# PCB.net
KiCad netlist of a schematic drawn in Altium Designer
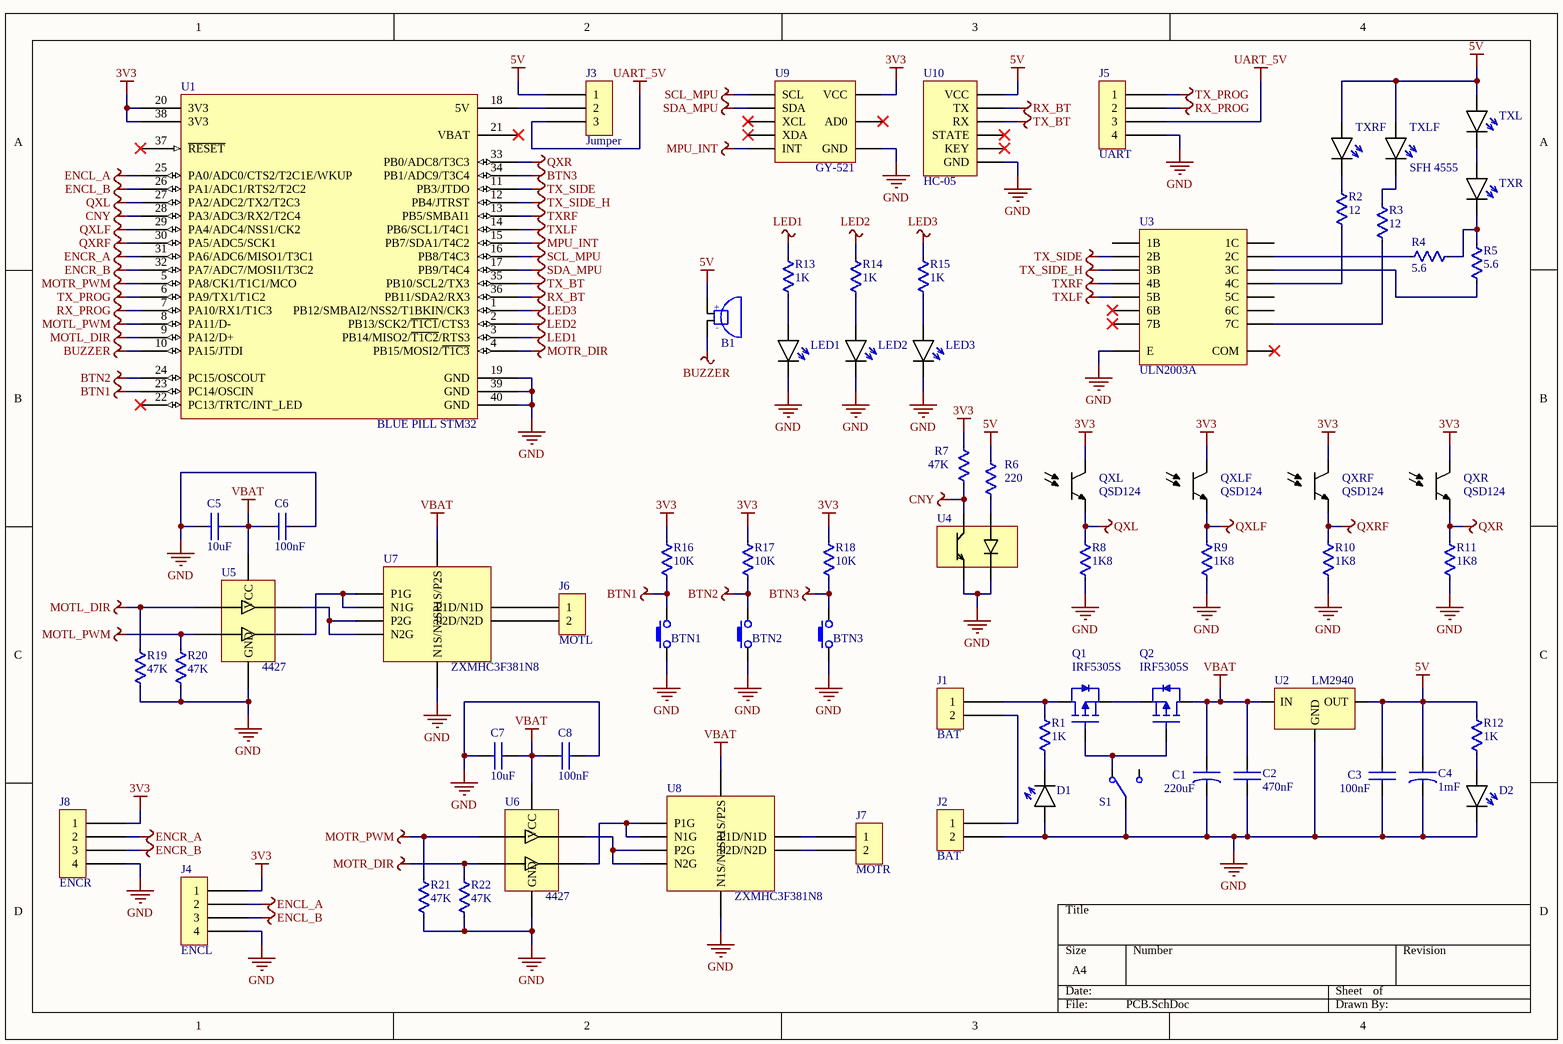
[diagram p0: PCB.SchDoc]

(export (version "E")
  (design (tool "Eeschema 10.0.6"))
  (components
    (comp (ref "B1")
      (value "BUZZER")
      (footprint "BUZZER-12MM")
      (libsource (lib "AltiumLibrary") (part "BUZZER-ACTIVE"))
    )
    (comp (ref "BTN1")
      (value "BUTTON")
      (footprint "TACT_SWITCH-SMALL-4PIN")
      (libsource (lib "AltiumLibrary") (part "BUTTON"))
    )
    (comp (ref "BTN2")
      (value "BUTTON")
      (footprint "TACT_SWITCH-SMALL-4PIN")
      (libsource (lib "AltiumLibrary") (part "BUTTON"))
    )
    (comp (ref "BTN3")
      (value "BUTTON")
      (footprint "TACT_SWITCH-SMALL-4PIN")
      (libsource (lib "AltiumLibrary") (part "BUTTON"))
    )
    (comp (ref "C1")
      (value "220uF")
      (footprint "CAP-ELEC-5x11x2mm")
      (fields (field (name "Comment") "CAP-ELEC"))
      (libsource (lib "AltiumLibrary") (part "CAP-ELEC"))
    )
    (comp (ref "C2")
      (value "470nF")
      (footprint "C1206")
      (fields (field (name "Comment") "CAP-CER"))
      (libsource (lib "AltiumLibrary") (part "CAP-CER"))
    )
    (comp (ref "C3")
      (value "100nF")
      (footprint "C1206")
      (fields (field (name "Comment") "CAP-CER"))
      (libsource (lib "AltiumLibrary") (part "CAP-CER"))
    )
    (comp (ref "C4")
      (value "1mF")
      (footprint "CAP-ELEC-5x11x2mm")
      (fields (field (name "Comment") "CAP-ELEC"))
      (libsource (lib "AltiumLibrary") (part "CAP-ELEC"))
    )
    (comp (ref "C5")
      (value "10uF")
      (footprint "C1206")
      (fields (field (name "Comment") "CAP-CER"))
      (libsource (lib "AltiumLibrary") (part "CAP-CER"))
    )
    (comp (ref "C6")
      (value "100nF")
      (footprint "C1206")
      (fields (field (name "Comment") "CAP-CER"))
      (libsource (lib "AltiumLibrary") (part "CAP-CER"))
    )
    (comp (ref "C7")
      (value "10uF")
      (footprint "C1206")
      (fields (field (name "Comment") "CAP-CER"))
      (libsource (lib "AltiumLibrary") (part "CAP-CER"))
    )
    (comp (ref "C8")
      (value "100nF")
      (footprint "C1206")
      (fields (field (name "Comment") "CAP-CER"))
      (libsource (lib "AltiumLibrary") (part "CAP-CER"))
    )
    (comp (ref "D1") (value "LED") (footprint "LED-3MM-GREEN") (libsource (lib "AltiumLibrary") (part "LED")))
    (comp (ref "D2") (value "LED") (footprint "LED-3MM-GREEN") (libsource (lib "AltiumLibrary") (part "LED")))
    (comp (ref "J1")
      (value "BAT")
      (footprint "HEADER 1x2")
      (libsource (lib "AltiumLibrary") (part "Header 1x2"))
    )
    (comp (ref "J2")
      (value "BAT")
      (footprint "HEADER 1x2")
      (libsource (lib "AltiumLibrary") (part "Header 1x2"))
    )
    (comp (ref "J3")
      (value "Jumper")
      (footprint "Header 1x3")
      (libsource (lib "AltiumLibrary") (part "Header 1x3"))
    )
    (comp (ref "J4")
      (value "ENCL")
      (footprint "Header 1x4")
      (libsource (lib "AltiumLibrary") (part "Header 1x4"))
    )
    (comp (ref "J5")
      (value "UART")
      (footprint "Header 1x4")
      (libsource (lib "AltiumLibrary") (part "Header 1x4"))
    )
    (comp (ref "J6") (value "MOTL") (footprint "HEADER 1x2") (libsource (lib "") (part "Header 1x2_1")))
    (comp (ref "J7") (value "MOTR") (footprint "HEADER 1x2") (libsource (lib "") (part "Header 1x2_1")))
    (comp (ref "J8")
      (value "ENCR")
      (footprint "Header 1x4")
      (libsource (lib "AltiumLibrary") (part "Header 1x4"))
    )
    (comp (ref "LED1")
      (value "LED")
      (footprint "LED-3MM-GREEN")
      (libsource (lib "AltiumLibrary") (part "LED"))
    )
    (comp (ref "LED2")
      (value "LED")
      (footprint "LED-3MM-GREEN")
      (libsource (lib "AltiumLibrary") (part "LED"))
    )
    (comp (ref "LED3")
      (value "LED")
      (footprint "LED-3MM-GREEN")
      (libsource (lib "AltiumLibrary") (part "LED"))
    )
    (comp (ref "Q1")
      (value "IRF5305S")
      (footprint "TO-263")
      (libsource (lib "AltiumLibrary") (part "P-MOSFET"))
    )
    (comp (ref "Q2")
      (value "IRF5305S")
      (footprint "TO-263")
      (libsource (lib "AltiumLibrary") (part "P-MOSFET"))
    )
    (comp (ref "QXL")
      (value "QSD124")
      (footprint "LED-5MM-RED-90-2")
      (libsource (lib "AltiumLibrary") (part "PHOTO NPN"))
    )
    (comp (ref "QXLF")
      (value "QSD124")
      (footprint "LED-5MM-RED-90")
      (libsource (lib "AltiumLibrary") (part "PHOTO NPN"))
    )
    (comp (ref "QXR")
      (value "QSD124")
      (footprint "LED-5MM-RED-90")
      (libsource (lib "AltiumLibrary") (part "PHOTO NPN"))
    )
    (comp (ref "QXRF")
      (value "QSD124")
      (footprint "LED-5MM-RED-90")
      (libsource (lib "AltiumLibrary") (part "PHOTO NPN"))
    )
    (comp (ref "R1")
      (value "1K")
      (footprint "R1206")
      (fields (field (name "Comment") "RES"))
      (libsource (lib "AltiumLibrary") (part "RES"))
    )
    (comp (ref "R2")
      (value "12")
      (footprint "R1206")
      (fields (field (name "Comment") "RES"))
      (libsource (lib "AltiumLibrary") (part "RES"))
    )
    (comp (ref "R3")
      (value "12")
      (footprint "R1206")
      (fields (field (name "Comment") "RES"))
      (libsource (lib "AltiumLibrary") (part "RES"))
    )
    (comp (ref "R4")
      (value "5.6")
      (footprint "R1206")
      (fields (field (name "Comment") "RES"))
      (libsource (lib "") (part "RES_1"))
    )
    (comp (ref "R5")
      (value "5.6")
      (footprint "R1206")
      (fields (field (name "Comment") "RES"))
      (libsource (lib "AltiumLibrary") (part "RES"))
    )
    (comp (ref "R6")
      (value "220")
      (footprint "R1206")
      (fields (field (name "Comment") "RES"))
      (libsource (lib "AltiumLibrary") (part "RES"))
    )
    (comp (ref "R7")
      (value "47K")
      (footprint "R1206")
      (fields (field (name "Comment") "RES"))
      (libsource (lib "AltiumLibrary") (part "RES"))
    )
    (comp (ref "R8")
      (value "1K8")
      (footprint "R1206")
      (fields (field (name "Comment") "RES"))
      (libsource (lib "AltiumLibrary") (part "RES"))
    )
    (comp (ref "R9")
      (value "1K8")
      (footprint "R1206")
      (fields (field (name "Comment") "RES"))
      (libsource (lib "AltiumLibrary") (part "RES"))
    )
    (comp (ref "R10")
      (value "1K8")
      (footprint "R1206")
      (fields (field (name "Comment") "RES"))
      (libsource (lib "AltiumLibrary") (part "RES"))
    )
    (comp (ref "R11")
      (value "1K8")
      (footprint "R1206")
      (fields (field (name "Comment") "RES"))
      (libsource (lib "AltiumLibrary") (part "RES"))
    )
    (comp (ref "R12")
      (value "1K")
      (footprint "R1206")
      (fields (field (name "Comment") "RES"))
      (libsource (lib "AltiumLibrary") (part "RES"))
    )
    (comp (ref "R13")
      (value "1K")
      (footprint "R1206")
      (fields (field (name "Comment") "RES"))
      (libsource (lib "AltiumLibrary") (part "RES"))
    )
    (comp (ref "R14")
      (value "1K")
      (footprint "R1206")
      (fields (field (name "Comment") "RES"))
      (libsource (lib "AltiumLibrary") (part "RES"))
    )
    (comp (ref "R15")
      (value "1K")
      (footprint "R1206")
      (fields (field (name "Comment") "RES"))
      (libsource (lib "AltiumLibrary") (part "RES"))
    )
    (comp (ref "R16")
      (value "10K")
      (footprint "R1206")
      (fields (field (name "Comment") "RES"))
      (libsource (lib "AltiumLibrary") (part "RES"))
    )
    (comp (ref "R17")
      (value "10K")
      (footprint "R1206")
      (fields (field (name "Comment") "RES"))
      (libsource (lib "AltiumLibrary") (part "RES"))
    )
    (comp (ref "R18")
      (value "10K")
      (footprint "R1206")
      (fields (field (name "Comment") "RES"))
      (libsource (lib "AltiumLibrary") (part "RES"))
    )
    (comp (ref "R19")
      (value "47K")
      (footprint "R1206")
      (fields (field (name "Comment") "RES"))
      (libsource (lib "AltiumLibrary") (part "RES"))
    )
    (comp (ref "R20")
      (value "47K")
      (footprint "R1206")
      (fields (field (name "Comment") "RES"))
      (libsource (lib "AltiumLibrary") (part "RES"))
    )
    (comp (ref "R21")
      (value "47K")
      (footprint "R1206")
      (fields (field (name "Comment") "RES"))
      (libsource (lib "AltiumLibrary") (part "RES"))
    )
    (comp (ref "R22")
      (value "47K")
      (footprint "R1206")
      (fields (field (name "Comment") "RES"))
      (libsource (lib "AltiumLibrary") (part "RES"))
    )
    (comp (ref "S1")
      (value "SLIDE-SWITCH")
      (footprint "SWITCH")
      (libsource (lib "AltiumLibrary") (part "SLIDE-SWITCH"))
    )
    (comp (ref "TXL")
      (value "LED")
      (footprint "LED-5MM-RED-90-2")
      (libsource (lib "AltiumLibrary") (part "LED"))
    )
    (comp (ref "TXLF")
      (value "SFH 4555")
      (footprint "LED-5MM-RED-90")
      (libsource (lib "AltiumLibrary") (part "LED"))
    )
    (comp (ref "TXR")
      (value "LED")
      (footprint "LED-5MM-RED-90")
      (libsource (lib "AltiumLibrary") (part "LED"))
    )
    (comp (ref "TXRF")
      (value "LED")
      (footprint "LED-5MM-RED-90")
      (libsource (lib "AltiumLibrary") (part "LED"))
    )
    (comp (ref "U1")
      (value "BLUE PILL STM32")
      (footprint "BLUE_PILL")
      (libsource (lib "AltiumLibrary") (part "BLUE PILL STM32"))
    )
    (comp (ref "U2") (value "LM2940") (footprint "TO-263") (libsource (lib "AltiumLibrary") (part "LM2940")))
    (comp (ref "U3")
      (value "ULN2003A")
      (footprint "SOIC-16-NARROW")
      (libsource (lib "AltiumLibrary") (part "ULN2003A"))
    )
    (comp (ref "U4")
      (value "QRE1113GR")
      (footprint "QRE1113GR")
      (fields (field (name "MF") "ON Semiconductor"))
      (libsource (lib "AltiumLibrary") (part "QRE1113GR"))
    )
    (comp (ref "U5") (value "4427") (footprint "SOIC-8") (libsource (lib "AltiumLibrary") (part "4427")))
    (comp (ref "U6") (value "4427") (footprint "SOIC-8") (libsource (lib "AltiumLibrary") (part "4427")))
    (comp (ref "U7")
      (value "ZXMHC3F381N8")
      (footprint "SOIC-8")
      (libsource (lib "AltiumLibrary") (part "ZXMHC3F381N8"))
    )
    (comp (ref "U8")
      (value "ZXMHC3F381N8")
      (footprint "SOIC-8")
      (libsource (lib "AltiumLibrary") (part "ZXMHC3F381N8"))
    )
    (comp (ref "U9")
      (value "GY-521")
      (footprint "GY-521")
      (libsource (lib "AltiumLibrary") (part "GY-521 (MPU6050)"))
    )
    (comp (ref "U10") (value "HC-05") (footprint "HC-05") (libsource (lib "AltiumLibrary") (part "HC-05")))
  )
  (nets
    (net (code "1") (name "3V3") (class "Default")
      (node (ref "J4") (pin "1") (pinfunction "1_1") (pintype "passive"))
      (node (ref "J8") (pin "1") (pinfunction "1_1") (pintype "passive"))
      (node (ref "QXL") (pin "C") (pinfunction "C_C") (pintype "passive"))
      (node (ref "QXLF") (pin "C") (pinfunction "C_C") (pintype "passive"))
      (node (ref "QXR") (pin "C") (pinfunction "C_C") (pintype "passive"))
      (node (ref "QXRF") (pin "C") (pinfunction "C_C") (pintype "passive"))
      (node (ref "R16") (pin "2") (pintype "passive"))
      (node (ref "R17") (pin "2") (pintype "passive"))
      (node (ref "R18") (pin "2") (pintype "passive"))
      (node (ref "R7") (pin "2") (pintype "passive"))
      (node (ref "U1") (pin "20") (pinfunction "3V3_20") (pintype "power_in"))
      (node (ref "U1") (pin "38") (pinfunction "3V3_38") (pintype "power_in"))
      (node (ref "U9") (pin "1") (pinfunction "VCC_1") (pintype "power_in"))
    )
    (net (code "2") (name "5V") (class "Default")
      (node (ref "B1") (pin "1") (pinfunction "+_1") (pintype "passive"))
      (node (ref "C3") (pin "2") (pintype "passive"))
      (node (ref "C4") (pin "1") (pintype "passive"))
      (node (ref "J3") (pin "1") (pinfunction "1_1") (pintype "passive"))
      (node (ref "R12") (pin "2") (pintype "passive"))
      (node (ref "R6") (pin "2") (pintype "passive"))
      (node (ref "TXL") (pin "A") (pintype "passive"))
      (node (ref "TXLF") (pin "A") (pintype "passive"))
      (node (ref "TXRF") (pin "A") (pintype "passive"))
      (node (ref "U10") (pin "2") (pinfunction "VCC_2") (pintype "power_in"))
      (node (ref "U2") (pin "3") (pinfunction "OUT_3") (pintype "power_in"))
    )
    (net (code "3") (name "BTN1") (class "Default")
      (node (ref "BTN1") (pin "2") (pintype "passive"))
      (node (ref "R16") (pin "1") (pintype "passive"))
      (node (ref "U1") (pin "23") (pinfunction "PC14/OSCIN_23") (pintype "bidirectional"))
    )
    (net (code "4") (name "BTN2") (class "Default")
      (node (ref "BTN2") (pin "2") (pintype "passive"))
      (node (ref "R17") (pin "1") (pintype "passive"))
      (node (ref "U1") (pin "24") (pinfunction "PC15/OSCOUT_24") (pintype "bidirectional"))
    )
    (net (code "5") (name "BTN3") (class "Default")
      (node (ref "BTN3") (pin "2") (pintype "passive"))
      (node (ref "R18") (pin "1") (pintype "passive"))
      (node (ref "U1") (pin "34") (pinfunction "PB1/ADC9/T3C4_34") (pintype "bidirectional"))
    )
    (net (code "6") (name "BUZZER") (class "Default")
      (node (ref "B1") (pin "2") (pinfunction "-_2") (pintype "passive"))
      (node (ref "U1") (pin "10") (pinfunction "PA15/JTDI_10") (pintype "bidirectional"))
    )
    (net (code "7") (name "CNY") (class "Default")
      (node (ref "R7") (pin "1") (pintype "passive"))
      (node (ref "U1") (pin "28") (pinfunction "PA3/ADC3/RX2/T2C4_28") (pintype "bidirectional"))
      (node (ref "U4") (pin "C") (pinfunction "C_C") (pintype "passive"))
    )
    (net (code "8") (name "ENCL_A") (class "Default")
      (node (ref "J4") (pin "2") (pinfunction "2_2") (pintype "passive"))
      (node (ref "U1") (pin "25") (pinfunction "PA0/ADC0/CTS2/T2C1E/WKUP_25") (pintype "bidirectional"))
    )
    (net (code "9") (name "ENCL_B") (class "Default")
      (node (ref "J4") (pin "3") (pinfunction "3_3") (pintype "passive"))
      (node (ref "U1") (pin "26") (pinfunction "PA1/ADC1/RTS2/T2C2_26") (pintype "bidirectional"))
    )
    (net (code "10") (name "ENCR_A") (class "Default")
      (node (ref "J8") (pin "2") (pinfunction "2_2") (pintype "passive"))
      (node (ref "U1") (pin "31") (pinfunction "PA6/ADC6/MISO1/T3C1_31") (pintype "bidirectional"))
    )
    (net (code "11") (name "ENCR_B") (class "Default")
      (node (ref "J8") (pin "3") (pinfunction "3_3") (pintype "passive"))
      (node (ref "U1") (pin "32") (pinfunction "PA7/ADC7/MOSI1/T3C2_32") (pintype "bidirectional"))
    )
    (net (code "12") (name "GND") (class "Default")
      (node (ref "BTN1") (pin "1") (pintype "passive"))
      (node (ref "BTN2") (pin "1") (pintype "passive"))
      (node (ref "BTN3") (pin "1") (pintype "passive"))
      (node (ref "C1") (pin "2") (pintype "passive"))
      (node (ref "C2") (pin "1") (pintype "passive"))
      (node (ref "C3") (pin "1") (pintype "passive"))
      (node (ref "C4") (pin "2") (pintype "passive"))
      (node (ref "C5") (pin "1") (pintype "passive"))
      (node (ref "C6") (pin "1") (pintype "passive"))
      (node (ref "C7") (pin "1") (pintype "passive"))
      (node (ref "C8") (pin "1") (pintype "passive"))
      (node (ref "D1") (pin "A") (pintype "passive"))
      (node (ref "D2") (pin "K") (pintype "passive"))
      (node (ref "J2") (pin "2") (pinfunction "2_2") (pintype "passive"))
      (node (ref "J4") (pin "4") (pinfunction "4_4") (pintype "passive"))
      (node (ref "J5") (pin "4") (pinfunction "4_4") (pintype "passive"))
      (node (ref "J8") (pin "4") (pinfunction "4_4") (pintype "passive"))
      (node (ref "LED1") (pin "K") (pintype "passive"))
      (node (ref "LED2") (pin "K") (pintype "passive"))
      (node (ref "LED3") (pin "K") (pintype "passive"))
      (node (ref "R10") (pin "1") (pintype "passive"))
      (node (ref "R11") (pin "1") (pintype "passive"))
      (node (ref "R19") (pin "1") (pintype "passive"))
      (node (ref "R20") (pin "1") (pintype "passive"))
      (node (ref "R21") (pin "1") (pintype "passive"))
      (node (ref "R22") (pin "1") (pintype "passive"))
      (node (ref "R8") (pin "1") (pintype "passive"))
      (node (ref "R9") (pin "1") (pintype "passive"))
      (node (ref "S1") (pin "2") (pintype "power_in"))
      (node (ref "U1") (pin "19") (pinfunction "GND_19") (pintype "power_in"))
      (node (ref "U1") (pin "39") (pinfunction "GND_39") (pintype "power_in"))
      (node (ref "U1") (pin "40") (pinfunction "GND_40") (pintype "power_in"))
      (node (ref "U10") (pin "3") (pinfunction "GND_3") (pintype "power_in"))
      (node (ref "U2") (pin "2") (pinfunction "GND_2") (pintype "power_in"))
      (node (ref "U3") (pin "8") (pinfunction "E_8") (pintype "power_in"))
      (node (ref "U4") (pin "E") (pinfunction "E_E") (pintype "passive"))
      (node (ref "U4") (pin "K") (pinfunction "K_K") (pintype "passive"))
      (node (ref "U5") (pin "3") (pinfunction "GND_3") (pintype "passive"))
      (node (ref "U6") (pin "3") (pinfunction "GND_3") (pintype "passive"))
      (node (ref "U7") (pin "3") (pinfunction "N1S/N2S_3") (pintype "passive"))
      (node (ref "U8") (pin "3") (pinfunction "N1S/N2S_3") (pintype "passive"))
      (node (ref "U9") (pin "2") (pinfunction "GND_2") (pintype "power_in"))
    )
    (net (code "13") (name "LED1") (class "Default")
      (node (ref "R13") (pin "2") (pintype "passive"))
      (node (ref "U1") (pin "3") (pinfunction "PB14/MISO2/~{T1C2}/RTS3_3") (pintype "bidirectional"))
    )
    (net (code "14") (name "LED2") (class "Default")
      (node (ref "R14") (pin "2") (pintype "passive"))
      (node (ref "U1") (pin "2") (pinfunction "PB13/SCK2/~{T1C1}/CTS3_2") (pintype "bidirectional"))
    )
    (net (code "15") (name "LED3") (class "Default")
      (node (ref "R15") (pin "2") (pintype "passive"))
      (node (ref "U1") (pin "1") (pinfunction "PB12/SMBAI2/NSS2/T1BKIN/CK3_1") (pintype "bidirectional"))
    )
    (net (code "16") (name "MOTL_DIR") (class "Default")
      (node (ref "R19") (pin "2") (pintype "passive"))
      (node (ref "U1") (pin "9") (pinfunction "PA12/D+_9") (pintype "bidirectional"))
      (node (ref "U5") (pin "2") (pinfunction "INA_2") (pintype "passive"))
    )
    (net (code "17") (name "MOTL_PWM") (class "Default")
      (node (ref "R20") (pin "2") (pintype "passive"))
      (node (ref "U1") (pin "8") (pinfunction "PA11/D-_8") (pintype "bidirectional"))
      (node (ref "U5") (pin "4") (pinfunction "INB_4") (pintype "passive"))
    )
    (net (code "18") (name "MOTR_DIR") (class "Default")
      (node (ref "R22") (pin "2") (pintype "passive"))
      (node (ref "U1") (pin "4") (pinfunction "PB15/MOSI2/~{T1C3}_4") (pintype "bidirectional"))
      (node (ref "U6") (pin "4") (pinfunction "INB_4") (pintype "passive"))
    )
    (net (code "19") (name "MOTR_PWM") (class "Default")
      (node (ref "R21") (pin "2") (pintype "passive"))
      (node (ref "U1") (pin "5") (pinfunction "PA8/CK1/T1C1/MCO_5") (pintype "bidirectional"))
      (node (ref "U6") (pin "2") (pinfunction "INA_2") (pintype "passive"))
    )
    (net (code "20") (name "MPU_INT") (class "Default")
      (node (ref "U1") (pin "15") (pinfunction "PB7/SDA1/T4C2_15") (pintype "bidirectional"))
      (node (ref "U9") (pin "8") (pinfunction "INT_8") (pintype "power_in"))
    )
    (net (code "21") (name "Net-(D1-PadK)") (class "Default")
      (node (ref "D1") (pin "K") (pintype "passive"))
      (node (ref "R1") (pin "1") (pintype "passive"))
    )
    (net (code "22") (name "Net-(D2-PadA)") (class "Default")
      (node (ref "D2") (pin "A") (pintype "passive"))
      (node (ref "R12") (pin "1") (pintype "passive"))
    )
    (net (code "23") (name "Net-(J1-Pad1)") (class "Default")
      (node (ref "J1") (pin "1") (pinfunction "1_1") (pintype "passive"))
      (node (ref "Q1") (pin "D") (pintype "passive"))
      (node (ref "R1") (pin "2") (pintype "passive"))
    )
    (net (code "24") (name "Net-(J1-Pad2)") (class "Default")
      (node (ref "J1") (pin "2") (pinfunction "2_2") (pintype "passive"))
      (node (ref "J2") (pin "1") (pinfunction "1_1") (pintype "passive"))
    )
    (net (code "25") (name "Net-(LED1-PadA)") (class "Default")
      (node (ref "LED1") (pin "A") (pintype "passive"))
      (node (ref "R13") (pin "1") (pintype "passive"))
    )
    (net (code "26") (name "Net-(LED2-PadA)") (class "Default")
      (node (ref "LED2") (pin "A") (pintype "passive"))
      (node (ref "R14") (pin "1") (pintype "passive"))
    )
    (net (code "27") (name "Net-(LED3-PadA)") (class "Default")
      (node (ref "LED3") (pin "A") (pintype "passive"))
      (node (ref "R15") (pin "1") (pintype "passive"))
    )
    (net (code "28") (name "Net-(Q1-PadG)") (class "Default")
      (node (ref "Q1") (pin "G") (pintype "passive"))
      (node (ref "Q2") (pin "G") (pintype "passive"))
      (node (ref "S1") (pin "1") (pintype "power_in"))
    )
    (net (code "29") (name "Net-(Q1-PadS)") (class "Default")
      (node (ref "Q1") (pin "S") (pintype "passive"))
      (node (ref "Q2") (pin "S") (pintype "passive"))
    )
    (net (code "30") (name "Net-(R2-Pad2)") (class "Default")
      (node (ref "R2") (pin "2") (pintype "passive"))
      (node (ref "TXRF") (pin "K") (pintype "passive"))
    )
    (net (code "31") (name "Net-(R3-Pad2)") (class "Default")
      (node (ref "R3") (pin "2") (pintype "passive"))
      (node (ref "TXLF") (pin "K") (pintype "passive"))
    )
    (net (code "32") (name "Net-(R4-Pad1)") (class "Default")
      (node (ref "R4") (pin "1") (pintype "passive"))
      (node (ref "R5") (pin "2") (pintype "passive"))
      (node (ref "TXR") (pin "K") (pintype "passive"))
    )
    (net (code "33") (name "Net-(R6-Pad1)") (class "Default")
      (node (ref "R6") (pin "1") (pintype "passive"))
      (node (ref "U4") (pin "A") (pinfunction "A_A") (pintype "passive"))
    )
    (net (code "34") (name "Net-(TXL-PadK)") (class "Default")
      (node (ref "TXL") (pin "K") (pintype "passive"))
      (node (ref "TXR") (pin "A") (pintype "passive"))
    )
    (net (code "35") (name "Net-(U1-5V)") (class "Default")
      (node (ref "J3") (pin "2") (pinfunction "2_2") (pintype "passive"))
      (node (ref "U1") (pin "18") (pinfunction "5V_18") (pintype "power_in"))
    )
    (net (code "36") (name "Net-(U3-2C)") (class "Default")
      (node (ref "R4") (pin "2") (pintype "passive"))
      (node (ref "U3") (pin "15") (pinfunction "2C_15") (pintype "power_in"))
    )
    (net (code "37") (name "Net-(U3-3C)") (class "Default")
      (node (ref "R5") (pin "1") (pintype "passive"))
      (node (ref "U3") (pin "14") (pinfunction "3C_14") (pintype "power_in"))
    )
    (net (code "38") (name "Net-(U3-4C)") (class "Default")
      (node (ref "R2") (pin "1") (pintype "passive"))
      (node (ref "U3") (pin "13") (pinfunction "4C_13") (pintype "power_in"))
    )
    (net (code "39") (name "Net-(U3-7C)") (class "Default")
      (node (ref "R3") (pin "1") (pintype "passive"))
      (node (ref "U3") (pin "10") (pinfunction "7C_10") (pintype "power_in"))
    )
    (net (code "40") (name "Net-(U5-OUTA)") (class "Default")
      (node (ref "U5") (pin "7") (pinfunction "OUTA_7") (pintype "passive"))
      (node (ref "U7") (pin "4") (pinfunction "N2G_4") (pintype "passive"))
      (node (ref "U7") (pin "5") (pinfunction "P2G_5") (pintype "passive"))
    )
    (net (code "41") (name "Net-(U5-OUTB)") (class "Default")
      (node (ref "U5") (pin "5") (pinfunction "OUTB_5") (pintype "passive"))
      (node (ref "U7") (pin "1") (pinfunction "N1G_1") (pintype "passive"))
      (node (ref "U7") (pin "8") (pinfunction "P1G_8") (pintype "passive"))
    )
    (net (code "42") (name "Net-(U6-OUTA)") (class "Default")
      (node (ref "U6") (pin "7") (pinfunction "OUTA_7") (pintype "passive"))
      (node (ref "U8") (pin "4") (pinfunction "N2G_4") (pintype "passive"))
      (node (ref "U8") (pin "5") (pinfunction "P2G_5") (pintype "passive"))
    )
    (net (code "43") (name "Net-(U6-OUTB)") (class "Default")
      (node (ref "U6") (pin "5") (pinfunction "OUTB_5") (pintype "passive"))
      (node (ref "U8") (pin "1") (pinfunction "N1G_1") (pintype "passive"))
      (node (ref "U8") (pin "8") (pinfunction "P1G_8") (pintype "passive"))
    )
    (net (code "44") (name "Net-(U7-P1D{slash}N1D)") (class "Default")
      (node (ref "J6") (pin "1") (pinfunction "1_1") (pintype "passive"))
      (node (ref "U7") (pin "2") (pinfunction "P1D/N1D_2") (pintype "passive"))
    )
    (net (code "45") (name "Net-(U7-P2D{slash}N2D)") (class "Default")
      (node (ref "J6") (pin "2") (pinfunction "2_2") (pintype "passive"))
      (node (ref "U7") (pin "6") (pinfunction "P2D/N2D_6") (pintype "passive"))
    )
    (net (code "46") (name "Net-(U8-P1D{slash}N1D)") (class "Default")
      (node (ref "J7") (pin "1") (pinfunction "1_1") (pintype "passive"))
      (node (ref "U8") (pin "2") (pinfunction "P1D/N1D_2") (pintype "passive"))
    )
    (net (code "47") (name "Net-(U8-P2D{slash}N2D)") (class "Default")
      (node (ref "J7") (pin "2") (pinfunction "2_2") (pintype "passive"))
      (node (ref "U8") (pin "6") (pinfunction "P2D/N2D_6") (pintype "passive"))
    )
    (net (code "48") (name "QXL") (class "Default")
      (node (ref "QXL") (pin "E") (pinfunction "E_E") (pintype "passive"))
      (node (ref "R8") (pin "2") (pintype "passive"))
      (node (ref "U1") (pin "27") (pinfunction "PA2/ADC2/TX2/T2C3_27") (pintype "bidirectional"))
    )
    (net (code "49") (name "QXLF") (class "Default")
      (node (ref "QXLF") (pin "E") (pinfunction "E_E") (pintype "passive"))
      (node (ref "R9") (pin "2") (pintype "passive"))
      (node (ref "U1") (pin "29") (pinfunction "PA4/ADC4/NSS1/CK2_29") (pintype "bidirectional"))
    )
    (net (code "50") (name "QXR") (class "Default")
      (node (ref "QXR") (pin "E") (pinfunction "E_E") (pintype "passive"))
      (node (ref "R11") (pin "2") (pintype "passive"))
      (node (ref "U1") (pin "33") (pinfunction "PB0/ADC8/T3C3_33") (pintype "bidirectional"))
    )
    (net (code "51") (name "QXRF") (class "Default")
      (node (ref "QXRF") (pin "E") (pinfunction "E_E") (pintype "passive"))
      (node (ref "R10") (pin "2") (pintype "passive"))
      (node (ref "U1") (pin "30") (pinfunction "PA5/ADC5/SCK1_30") (pintype "bidirectional"))
    )
    (net (code "52") (name "RX_BT") (class "Default")
      (node (ref "U1") (pin "36") (pinfunction "PB11/SDA2/RX3_36") (pintype "bidirectional"))
      (node (ref "U10") (pin "4") (pinfunction "TX_4") (pintype "power_in"))
    )
    (net (code "53") (name "RX_PROG") (class "Default")
      (node (ref "J5") (pin "2") (pinfunction "2_2") (pintype "passive"))
      (node (ref "U1") (pin "7") (pinfunction "PA10/RX1/T1C3_7") (pintype "bidirectional"))
    )
    (net (code "54") (name "SCL_MPU") (class "Default")
      (node (ref "U1") (pin "16") (pinfunction "PB8/T4C3_16") (pintype "bidirectional"))
      (node (ref "U9") (pin "3") (pinfunction "SCL_3") (pintype "power_in"))
    )
    (net (code "55") (name "SDA_MPU") (class "Default")
      (node (ref "U1") (pin "17") (pinfunction "PB9/T4C4_17") (pintype "bidirectional"))
      (node (ref "U9") (pin "4") (pinfunction "SDA_4") (pintype "power_in"))
    )
    (net (code "56") (name "TXLF") (class "Default")
      (node (ref "U1") (pin "14") (pinfunction "PB6/SCL1/T4C1_14") (pintype "bidirectional"))
      (node (ref "U3") (pin "5") (pinfunction "5B_5") (pintype "power_in"))
    )
    (net (code "57") (name "TXRF") (class "Default")
      (node (ref "U1") (pin "13") (pinfunction "PB5/SMBAI1_13") (pintype "bidirectional"))
      (node (ref "U3") (pin "4") (pinfunction "4B_4") (pintype "power_in"))
    )
    (net (code "58") (name "TX_BT") (class "Default")
      (node (ref "U1") (pin "35") (pinfunction "PB10/SCL2/TX3_35") (pintype "bidirectional"))
      (node (ref "U10") (pin "5") (pinfunction "RX_5") (pintype "power_in"))
    )
    (net (code "59") (name "TX_PROG") (class "Default")
      (node (ref "J5") (pin "1") (pinfunction "1_1") (pintype "passive"))
      (node (ref "U1") (pin "6") (pinfunction "PA9/TX1/T1C2_6") (pintype "bidirectional"))
    )
    (net (code "60") (name "TX_SIDE") (class "Default")
      (node (ref "U1") (pin "11") (pinfunction "PB3/JTDO_11") (pintype "bidirectional"))
      (node (ref "U3") (pin "2") (pinfunction "2B_2") (pintype "power_in"))
    )
    (net (code "61") (name "TX_SIDE_H") (class "Default")
      (node (ref "U1") (pin "12") (pinfunction "PB4/JTRST_12") (pintype "bidirectional"))
      (node (ref "U3") (pin "3") (pinfunction "3B_3") (pintype "power_in"))
    )
    (net (code "62") (name "UART_5V") (class "Default")
      (node (ref "J3") (pin "3") (pinfunction "3_3") (pintype "passive"))
      (node (ref "J5") (pin "3") (pinfunction "3_3") (pintype "passive"))
    )
    (net (code "63") (name "VBAT") (class "Default")
      (node (ref "C1") (pin "1") (pintype "passive"))
      (node (ref "C2") (pin "2") (pintype "passive"))
      (node (ref "C5") (pin "2") (pintype "passive"))
      (node (ref "C6") (pin "2") (pintype "passive"))
      (node (ref "C7") (pin "2") (pintype "passive"))
      (node (ref "C8") (pin "2") (pintype "passive"))
      (node (ref "Q2") (pin "D") (pintype "passive"))
      (node (ref "U2") (pin "1") (pinfunction "IN_1") (pintype "power_in"))
      (node (ref "U5") (pin "6") (pinfunction "VCC_6") (pintype "passive"))
      (node (ref "U6") (pin "6") (pinfunction "VCC_6") (pintype "passive"))
      (node (ref "U7") (pin "7") (pinfunction "P1S/P2S_7") (pintype "passive"))
      (node (ref "U8") (pin "7") (pinfunction "P1S/P2S_7") (pintype "passive"))
    )
    (net (code "64") (name "unconnected-(S1-Pad3)") (class "Default")
      (node (ref "S1") (pin "3") (pintype "power_in"))
    )
    (net (code "65") (name "unconnected-(U1-PC13{slash}TRTC{slash}INT_LED-Pad22)") (class "Default")
      (node (ref "U1") (pin "22") (pinfunction "PC13/TRTC/INT_LED_22") (pintype "bidirectional+no_connect"))
    )
    (net (code "66") (name "unconnected-(U1-VBAT-Pad21)") (class "Default")
      (node (ref "U1") (pin "21") (pinfunction "VBAT_21") (pintype "power_in+no_connect"))
    )
    (net (code "67") (name "unconnected-(U1-~{RESET}-Pad37)") (class "Default")
      (node (ref "U1") (pin "37") (pinfunction "~{RESET}_37") (pintype "input+no_connect"))
    )
    (net (code "68") (name "unconnected-(U3-1B-Pad1)") (class "Default")
      (node (ref "U3") (pin "1") (pinfunction "1B_1") (pintype "power_in"))
    )
    (net (code "69") (name "unconnected-(U3-1C-Pad16)") (class "Default")
      (node (ref "U3") (pin "16") (pinfunction "1C_16") (pintype "power_in"))
    )
    (net (code "70") (name "unconnected-(U3-5C-Pad12)") (class "Default")
      (node (ref "U3") (pin "12") (pinfunction "5C_12") (pintype "power_in"))
    )
    (net (code "71") (name "unconnected-(U3-6B-Pad6)") (class "Default")
      (node (ref "U3") (pin "6") (pinfunction "6B_6") (pintype "power_in+no_connect"))
    )
    (net (code "72") (name "unconnected-(U3-6C-Pad11)") (class "Default")
      (node (ref "U3") (pin "11") (pinfunction "6C_11") (pintype "power_in"))
    )
    (net (code "73") (name "unconnected-(U3-7B-Pad7)") (class "Default")
      (node (ref "U3") (pin "7") (pinfunction "7B_7") (pintype "power_in+no_connect"))
    )
    (net (code "74") (name "unconnected-(U3-COM-Pad9)") (class "Default")
      (node (ref "U3") (pin "9") (pinfunction "COM_9") (pintype "power_in+no_connect"))
    )
    (net (code "75") (name "unconnected-(U9-AD0-Pad7)") (class "Default")
      (node (ref "U9") (pin "7") (pinfunction "AD0_7") (pintype "power_in+no_connect"))
    )
    (net (code "76") (name "unconnected-(U9-XCL-Pad5)") (class "Default")
      (node (ref "U9") (pin "5") (pinfunction "XCL_5") (pintype "power_in+no_connect"))
    )
    (net (code "77") (name "unconnected-(U9-XDA-Pad6)") (class "Default")
      (node (ref "U9") (pin "6") (pinfunction "XDA_6") (pintype "power_in+no_connect"))
    )
    (net (code "78") (name "unconnected-(U10-KEY-Pad1)") (class "Default")
      (node (ref "U10") (pin "1") (pinfunction "KEY_1") (pintype "power_in+no_connect"))
    )
    (net (code "79") (name "unconnected-(U10-STATE-Pad6)") (class "Default")
      (node (ref "U10") (pin "6") (pinfunction "STATE_6") (pintype "power_in+no_connect"))
    )
  )
)
